# Breakout_U_V_v_1_0.net
KiCad netlist of a schematic drawn in EAGLE
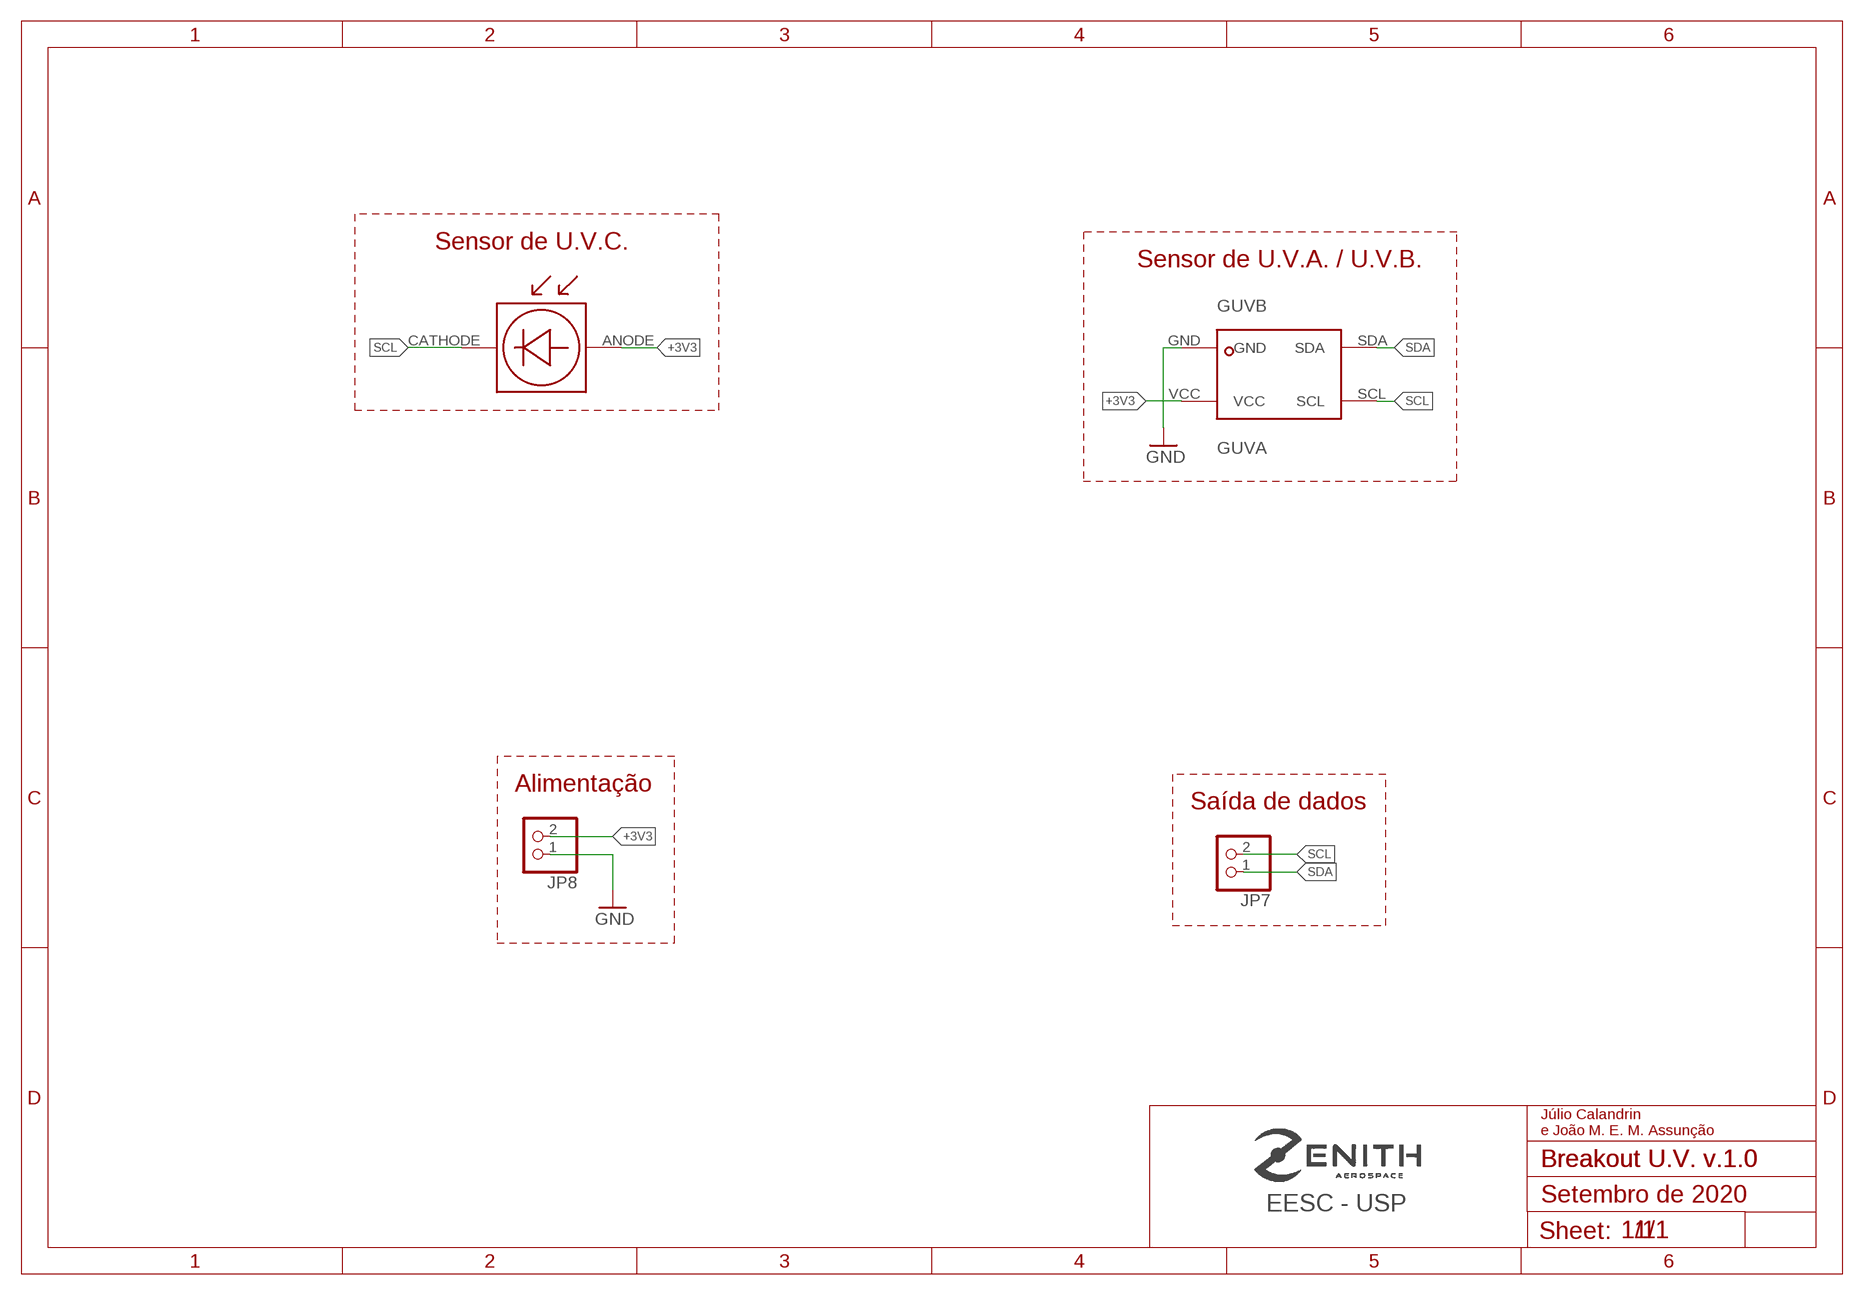
[diagram p0: schematic, sheet 1]

(export (version "E")
  (design (tool "Eeschema 10.0.6"))
  (components
    (comp (ref "GUVB")
      (value "GUVA")
      (footprint "eagle-import:GUV_A_B")
      (libsource (lib "eagle-import") (part "GUVA-C32SM"))
    )
    (comp (ref "JP7")
      (value "PINHD-1X2")
      (footprint "eagle-import:1X02(PAD_REDUZIDO)")
      (libsource (lib "eagle-import") (part "PINHD-1X2"))
    )
    (comp (ref "JP8")
      (value "PINHD-1X2")
      (footprint "eagle-import:1X02(PAD_REDUZIDO)")
      (libsource (lib "eagle-import") (part "PINHD-1X2"))
    )
    (comp (ref "U$1")
      (value "GUVC-S10GD")
      (footprint "eagle-import:GUV_C")
      (libsource (lib "eagle-import") (part "GUVC-S10GD"))
    )
  )
  (nets
    (net (code "1") (name "+3V3") (class "Default")
      (node (ref "GUVB") (pin "VCC") (pinfunction "VCC_VCC") (pintype "bidirectional"))
      (node (ref "JP8") (pin "2") (pinfunction "2_2") (pintype "passive"))
      (node (ref "U$1") (pin "ANODE") (pinfunction "ANODE_ANODE") (pintype "bidirectional"))
    )
    (net (code "2") (name "GND") (class "Default")
      (node (ref "GUVB") (pin "GND") (pinfunction "GND_GND") (pintype "bidirectional"))
      (node (ref "JP8") (pin "1") (pinfunction "1_1") (pintype "passive"))
    )
    (net (code "3") (name "SCL") (class "Default")
      (node (ref "GUVB") (pin "SCL") (pinfunction "SCL_SCL") (pintype "bidirectional"))
      (node (ref "JP7") (pin "2") (pinfunction "2_2") (pintype "passive"))
      (node (ref "U$1") (pin "CATHODE") (pinfunction "CATHODE_CATHODE") (pintype "bidirectional"))
    )
    (net (code "4") (name "SDA") (class "Default")
      (node (ref "GUVB") (pin "SDA") (pinfunction "SDA_SDA") (pintype "bidirectional"))
      (node (ref "JP7") (pin "1") (pinfunction "1_1") (pintype "passive"))
    )
  )
)
